# Transformer_less_5v_100mA.net
KiCad netlist of a schematic drawn in EAGLE
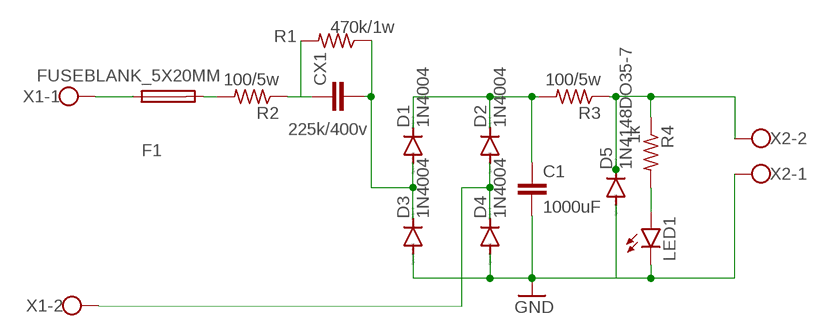
[diagram p0: schematic, sheet 1]

(export (version "E")
  (design (tool "Eeschema 10.0.6"))
  (components
    (comp (ref "C1")
      (value "1000uF")
      (footprint "eagle-import:C025-060X050")
      (libsource (lib "eagle-import") (part "C-EU025-060X050"))
    )
    (comp (ref "CX1")
      (value "225k/400v")
      (footprint "eagle-import:XC15B10")
      (libsource (lib "eagle-import") (part "CXXC15B10"))
    )
    (comp (ref "D1")
      (value "1N4004")
      (footprint "eagle-import:DO41-10")
      (libsource (lib "eagle-import") (part "1N4004"))
    )
    (comp (ref "D2")
      (value "1N4004")
      (footprint "eagle-import:DO41-10")
      (libsource (lib "eagle-import") (part "1N4004"))
    )
    (comp (ref "D3")
      (value "1N4004")
      (footprint "eagle-import:DO41-10")
      (libsource (lib "eagle-import") (part "1N4004"))
    )
    (comp (ref "D4")
      (value "1N4004")
      (footprint "eagle-import:DO41-10")
      (libsource (lib "eagle-import") (part "1N4004"))
    )
    (comp (ref "D5")
      (value "1N4148DO35-7")
      (footprint "eagle-import:DO35-7")
      (libsource (lib "eagle-import") (part "1N4148DO35-7"))
    )
    (comp (ref "F1")
      (value "FUSEBLANK_5X20MM")
      (footprint "eagle-import:FUSE_HOLDER_5X20MM")
      (libsource (lib "eagle-import") (part "FUSEBLANK_5X20MM"))
    )
    (comp (ref "LED1")
      (value "LED5MM")
      (footprint "eagle-import:LED5MM")
      (libsource (lib "eagle-import") (part "LED5MM"))
    )
    (comp (ref "R1")
      (value "470k/1w")
      (footprint "eagle-import:0414_15")
      (libsource (lib "eagle-import") (part "R-US_0414/15"))
    )
    (comp (ref "R2")
      (value "100/5w")
      (footprint "eagle-import:0617_22")
      (libsource (lib "eagle-import") (part "R-US_0617/22"))
    )
    (comp (ref "R3")
      (value "100/5w")
      (footprint "eagle-import:0617_22")
      (libsource (lib "eagle-import") (part "R-US_0617/22"))
    )
    (comp (ref "R4")
      (value "1k")
      (footprint "eagle-import:0207_7")
      (libsource (lib "eagle-import") (part "R-US_0207/7"))
    )
    (comp (ref "X1")
      (value "W237-102")
      (footprint "eagle-import:W237-102")
      (fields (field (name "MPN") "237-102"))
      (libsource (lib "eagle-import") (part "W237-102"))
    )
    (comp (ref "X2")
      (value "W237-102")
      (footprint "eagle-import:W237-102")
      (fields (field (name "MPN") "237-102"))
      (libsource (lib "eagle-import") (part "W237-102"))
    )
  )
  (nets
    (net (code "1") (name "GND") (class "Default")
      (node (ref "C1") (pin "2") (pinfunction "2_2") (pintype "passive"))
      (node (ref "D3") (pin "A") (pinfunction "A_A") (pintype "passive"))
      (node (ref "D4") (pin "A") (pinfunction "A_A") (pintype "passive"))
      (node (ref "D5") (pin "A") (pinfunction "A_A") (pintype "passive"))
      (node (ref "LED1") (pin "K") (pinfunction "C_K") (pintype "passive"))
      (node (ref "X2") (pin "1") (pinfunction "KL_1") (pintype "passive"))
    )
    (net (code "2") (name "Net-(C1-Pad1)") (class "Default")
      (node (ref "C1") (pin "1") (pinfunction "1_1") (pintype "passive"))
      (node (ref "D1") (pin "C") (pinfunction "C_C") (pintype "passive"))
      (node (ref "D2") (pin "C") (pinfunction "C_C") (pintype "passive"))
      (node (ref "R3") (pin "2") (pinfunction "2_2") (pintype "passive"))
    )
    (net (code "3") (name "Net-(CX1-Pad1)") (class "Default")
      (node (ref "CX1") (pin "1") (pinfunction "1_1") (pintype "passive"))
      (node (ref "R1") (pin "2") (pinfunction "2_2") (pintype "passive"))
      (node (ref "R2") (pin "1") (pinfunction "1_1") (pintype "passive"))
    )
    (net (code "4") (name "Net-(CX1-Pad2)") (class "Default")
      (node (ref "CX1") (pin "2") (pinfunction "2_2") (pintype "passive"))
      (node (ref "D1") (pin "A") (pinfunction "A_A") (pintype "passive"))
      (node (ref "D3") (pin "C") (pinfunction "C_C") (pintype "passive"))
      (node (ref "R1") (pin "1") (pinfunction "1_1") (pintype "passive"))
    )
    (net (code "5") (name "Net-(F1-Pad2)") (class "Default")
      (node (ref "F1") (pin "2") (pinfunction "2_2") (pintype "passive"))
      (node (ref "R2") (pin "2") (pinfunction "2_2") (pintype "passive"))
    )
    (net (code "6") (name "Net-(LED1-PadA)") (class "Default")
      (node (ref "LED1") (pin "A") (pinfunction "A_A") (pintype "passive"))
      (node (ref "R4") (pin "2") (pinfunction "2_2") (pintype "passive"))
    )
    (net (code "7") (name "Net-(X1A-KL)") (class "Default")
      (node (ref "F1") (pin "1") (pinfunction "1_1") (pintype "passive"))
      (node (ref "X1") (pin "1") (pinfunction "KL_1") (pintype "passive"))
    )
    (net (code "8") (name "Net-(X1B-KL)") (class "Default")
      (node (ref "D2") (pin "A") (pinfunction "A_A") (pintype "passive"))
      (node (ref "D4") (pin "C") (pinfunction "C_C") (pintype "passive"))
      (node (ref "X1") (pin "2") (pinfunction "KL_2") (pintype "passive"))
    )
    (net (code "9") (name "Net-(X2B-KL)") (class "Default")
      (node (ref "D5") (pin "C") (pinfunction "C_C") (pintype "passive"))
      (node (ref "R3") (pin "1") (pinfunction "1_1") (pintype "passive"))
      (node (ref "R4") (pin "1") (pinfunction "1_1") (pintype "passive"))
      (node (ref "X2") (pin "2") (pinfunction "KL_2") (pintype "passive"))
    )
  )
)
